# OSO-MISC-22-006_LCD_Wing.net
KiCad netlist of a schematic drawn in EAGLE
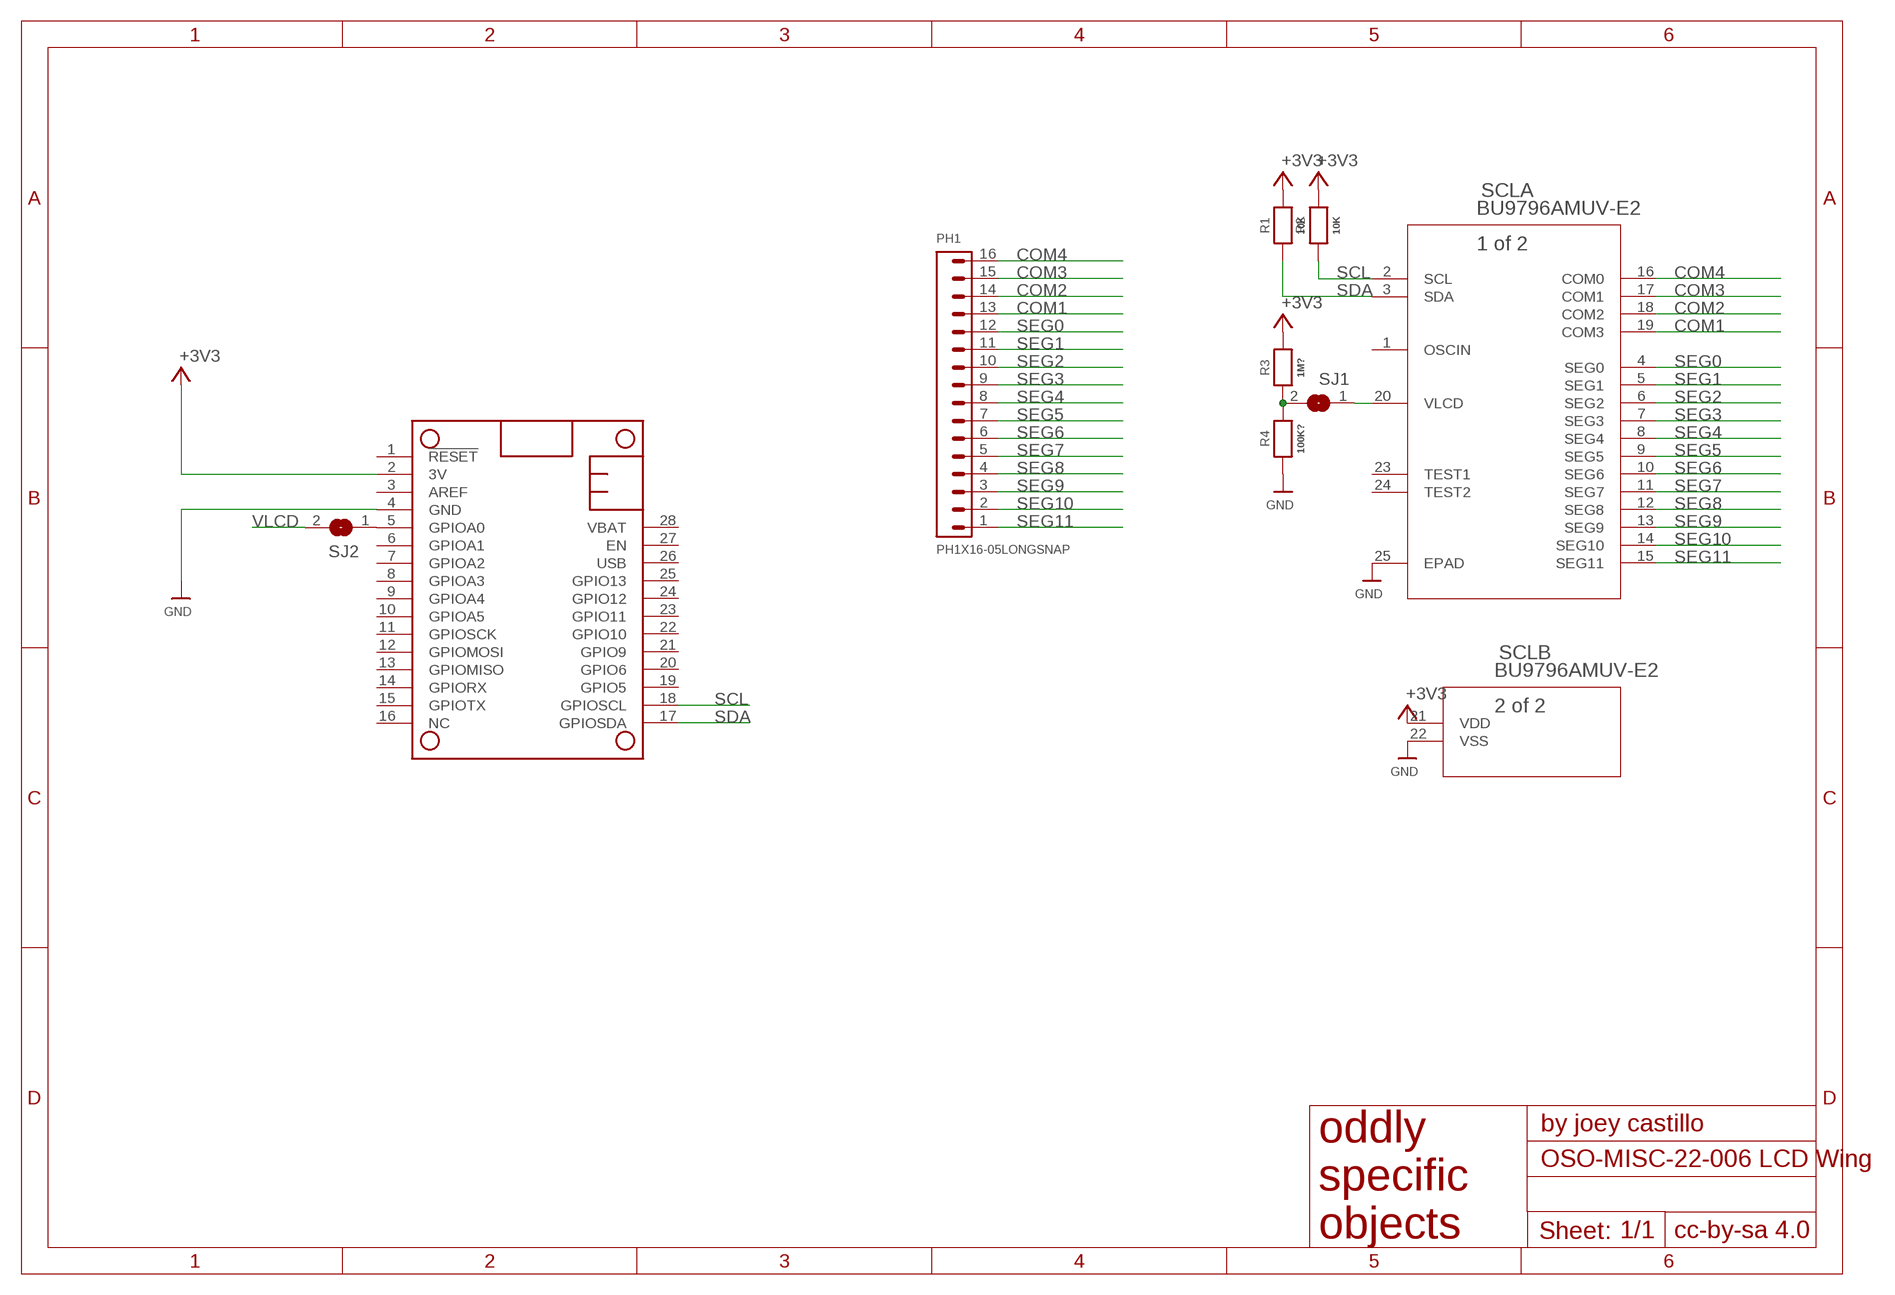
[diagram p0: schematic, sheet 1]

(export (version "E")
  (design (tool "Eeschema 10.0.6"))
  (components
    (comp (ref "MS1")
      (value "FEATHERWING")
      (footprint "eagle-import:FEATHERWING")
      (libsource (lib "eagle-import") (part "FEATHERWING"))
    )
    (comp (ref "PH1")
      (value "PH1X16-05LONGSNAP")
      (footprint "eagle-import:PHLS005-1-16")
      (libsource (lib "eagle-import") (part "PH1X16-05LONGSNAP"))
    )
    (comp (ref "R1")
      (value "10K")
      (footprint "eagle-import:_0805MP")
      (libsource (lib "eagle-import") (part "RESISTOR_0805MP"))
    )
    (comp (ref "R2")
      (value "10K")
      (footprint "eagle-import:_0805MP")
      (libsource (lib "eagle-import") (part "RESISTOR_0805MP"))
    )
    (comp (ref "R3")
      (value "1M?")
      (footprint "eagle-import:_0805MP")
      (libsource (lib "eagle-import") (part "RESISTOR_0805MP"))
    )
    (comp (ref "R4")
      (value "100K?")
      (footprint "eagle-import:_0805MP")
      (libsource (lib "eagle-import") (part "RESISTOR_0805MP"))
    )
    (comp (ref "SCL")
      (value "BU9796AMUV-E2")
      (footprint "eagle-import:VQFN024V4040_ROM")
      (fields (field (name "COPYRIGHT") "Copyright (C) 2022 Ultra Librarian. All rights reserved."))
      (libsource (lib "eagle-import") (part "BU9796AMUV-E2"))
    )
    (comp (ref "SJ1")
      (value "SOLDERJUMPERCLOSED")
      (footprint "eagle-import:SOLDERJUMPER_CLOSEDWIRE")
      (libsource (lib "eagle-import") (part "SOLDERJUMPERCLOSED"))
    )
    (comp (ref "SJ2")
      (value "SOLDERJUMPER")
      (footprint "eagle-import:SOLDERJUMPER_ARROW_NOPASTE")
      (libsource (lib "eagle-import") (part "SOLDERJUMPER"))
    )
  )
  (nets
    (net (code "1") (name "+3V3") (class "Default")
      (node (ref "MS1") (pin "2") (pinfunction "3V_2") (pintype "power_in"))
      (node (ref "R1") (pin "1") (pinfunction "1_1") (pintype "passive"))
      (node (ref "R2") (pin "1") (pinfunction "1_1") (pintype "passive"))
      (node (ref "R3") (pin "1") (pinfunction "1_1") (pintype "passive"))
      (node (ref "SCL") (pin "21") (pinfunction "VDD_21") (pintype "power_in"))
    )
    (net (code "2") (name "/COM1") (class "Default")
      (node (ref "PH1") (pin "13") (pinfunction "13_13") (pintype "bidirectional"))
      (node (ref "SCL") (pin "19") (pinfunction "COM3_19") (pintype "bidirectional"))
    )
    (net (code "3") (name "/COM2") (class "Default")
      (node (ref "PH1") (pin "14") (pinfunction "14_14") (pintype "bidirectional"))
      (node (ref "SCL") (pin "18") (pinfunction "COM2_18") (pintype "bidirectional"))
    )
    (net (code "4") (name "/COM3") (class "Default")
      (node (ref "PH1") (pin "15") (pinfunction "15_15") (pintype "bidirectional"))
      (node (ref "SCL") (pin "17") (pinfunction "COM1_17") (pintype "bidirectional"))
    )
    (net (code "5") (name "/COM4") (class "Default")
      (node (ref "PH1") (pin "16") (pinfunction "16_16") (pintype "bidirectional"))
      (node (ref "SCL") (pin "16") (pinfunction "COM0_16") (pintype "bidirectional"))
    )
    (net (code "6") (name "/SCL") (class "Default")
      (node (ref "MS1") (pin "18") (pinfunction "GPIOSCL_18") (pintype "bidirectional"))
      (node (ref "R2") (pin "2") (pinfunction "2_2") (pintype "passive"))
      (node (ref "SCL") (pin "2") (pinfunction "SCL_2") (pintype "passive"))
    )
    (net (code "7") (name "/SDA") (class "Default")
      (node (ref "MS1") (pin "17") (pinfunction "GPIOSDA_17") (pintype "bidirectional"))
      (node (ref "R1") (pin "2") (pinfunction "2_2") (pintype "passive"))
      (node (ref "SCL") (pin "3") (pinfunction "SDA_3") (pintype "passive"))
    )
    (net (code "8") (name "/SEG0") (class "Default")
      (node (ref "PH1") (pin "12") (pinfunction "12_12") (pintype "bidirectional"))
      (node (ref "SCL") (pin "4") (pinfunction "SEG0_4") (pintype "bidirectional"))
    )
    (net (code "9") (name "/SEG1") (class "Default")
      (node (ref "PH1") (pin "11") (pinfunction "11_11") (pintype "bidirectional"))
      (node (ref "SCL") (pin "5") (pinfunction "SEG1_5") (pintype "bidirectional"))
    )
    (net (code "10") (name "/SEG2") (class "Default")
      (node (ref "PH1") (pin "10") (pinfunction "10_10") (pintype "bidirectional"))
      (node (ref "SCL") (pin "6") (pinfunction "SEG2_6") (pintype "bidirectional"))
    )
    (net (code "11") (name "/SEG3") (class "Default")
      (node (ref "PH1") (pin "9") (pinfunction "9_9") (pintype "bidirectional"))
      (node (ref "SCL") (pin "7") (pinfunction "SEG3_7") (pintype "bidirectional"))
    )
    (net (code "12") (name "/SEG4") (class "Default")
      (node (ref "PH1") (pin "8") (pinfunction "8_8") (pintype "bidirectional"))
      (node (ref "SCL") (pin "8") (pinfunction "SEG4_8") (pintype "bidirectional"))
    )
    (net (code "13") (name "/SEG5") (class "Default")
      (node (ref "PH1") (pin "7") (pinfunction "7_7") (pintype "bidirectional"))
      (node (ref "SCL") (pin "9") (pinfunction "SEG5_9") (pintype "bidirectional"))
    )
    (net (code "14") (name "/SEG6") (class "Default")
      (node (ref "PH1") (pin "6") (pinfunction "6_6") (pintype "bidirectional"))
      (node (ref "SCL") (pin "10") (pinfunction "SEG6_10") (pintype "bidirectional"))
    )
    (net (code "15") (name "/SEG7") (class "Default")
      (node (ref "PH1") (pin "5") (pinfunction "5_5") (pintype "bidirectional"))
      (node (ref "SCL") (pin "11") (pinfunction "SEG7_11") (pintype "bidirectional"))
    )
    (net (code "16") (name "/SEG8") (class "Default")
      (node (ref "PH1") (pin "4") (pinfunction "4_4") (pintype "bidirectional"))
      (node (ref "SCL") (pin "12") (pinfunction "SEG8_12") (pintype "bidirectional"))
    )
    (net (code "17") (name "/SEG9") (class "Default")
      (node (ref "PH1") (pin "3") (pinfunction "3_3") (pintype "bidirectional"))
      (node (ref "SCL") (pin "13") (pinfunction "SEG9_13") (pintype "bidirectional"))
    )
    (net (code "18") (name "/SEG10") (class "Default")
      (node (ref "PH1") (pin "2") (pinfunction "2_2") (pintype "bidirectional"))
      (node (ref "SCL") (pin "14") (pinfunction "SEG10_14") (pintype "bidirectional"))
    )
    (net (code "19") (name "/SEG11") (class "Default")
      (node (ref "PH1") (pin "1") (pinfunction "1_1") (pintype "bidirectional"))
      (node (ref "SCL") (pin "15") (pinfunction "SEG11_15") (pintype "bidirectional"))
    )
    (net (code "20") (name "/USB") (class "Default")
      (node (ref "MS1") (pin "26") (pinfunction "USB_26") (pintype "power_in"))
    )
    (net (code "21") (name "/VBAT") (class "Default")
      (node (ref "MS1") (pin "28") (pinfunction "VBAT_28") (pintype "power_in"))
    )
    (net (code "22") (name "/VLCD") (class "Default")
      (node (ref "SCL") (pin "20") (pinfunction "VLCD_20") (pintype "passive"))
      (node (ref "SJ1") (pin "1") (pinfunction "1_1") (pintype "passive"))
      (node (ref "SJ2") (pin "2") (pinfunction "2_2") (pintype "passive"))
    )
    (net (code "23") (name "GND") (class "Default")
      (node (ref "MS1") (pin "4") (pinfunction "GND_4") (pintype "power_in"))
      (node (ref "R4") (pin "2") (pinfunction "2_2") (pintype "passive"))
      (node (ref "SCL") (pin "22") (pinfunction "VSS_22") (pintype "passive"))
      (node (ref "SCL") (pin "25") (pinfunction "EPAD_25") (pintype "passive"))
    )
    (net (code "24") (name "Net-(MS1-GPIOA0)") (class "Default")
      (node (ref "MS1") (pin "5") (pinfunction "GPIOA0_5") (pintype "bidirectional"))
      (node (ref "SJ2") (pin "1") (pinfunction "1_1") (pintype "passive"))
    )
    (net (code "25") (name "Net-(R3-Pad2)") (class "Default")
      (node (ref "R3") (pin "2") (pinfunction "2_2") (pintype "passive"))
      (node (ref "R4") (pin "1") (pinfunction "1_1") (pintype "passive"))
      (node (ref "SJ1") (pin "2") (pinfunction "2_2") (pintype "passive"))
    )
    (net (code "26") (name "unconnected-(MS1-AREF-Pad3)") (class "Default")
      (node (ref "MS1") (pin "3") (pinfunction "AREF_3") (pintype "passive"))
    )
    (net (code "27") (name "unconnected-(MS1-EN-Pad27)") (class "Default")
      (node (ref "MS1") (pin "27") (pinfunction "EN_27") (pintype "passive"))
    )
    (net (code "28") (name "unconnected-(MS1-GPIO5-Pad19)") (class "Default")
      (node (ref "MS1") (pin "19") (pinfunction "GPIO5_19") (pintype "bidirectional"))
    )
    (net (code "29") (name "unconnected-(MS1-GPIO6-Pad20)") (class "Default")
      (node (ref "MS1") (pin "20") (pinfunction "GPIO6_20") (pintype "bidirectional"))
    )
    (net (code "30") (name "unconnected-(MS1-GPIO9-Pad21)") (class "Default")
      (node (ref "MS1") (pin "21") (pinfunction "GPIO9_21") (pintype "bidirectional"))
    )
    (net (code "31") (name "unconnected-(MS1-GPIO10-Pad22)") (class "Default")
      (node (ref "MS1") (pin "22") (pinfunction "GPIO10_22") (pintype "bidirectional"))
    )
    (net (code "32") (name "unconnected-(MS1-GPIO11-Pad23)") (class "Default")
      (node (ref "MS1") (pin "23") (pinfunction "GPIO11_23") (pintype "bidirectional"))
    )
    (net (code "33") (name "unconnected-(MS1-GPIO12-Pad24)") (class "Default")
      (node (ref "MS1") (pin "24") (pinfunction "GPIO12_24") (pintype "bidirectional"))
    )
    (net (code "34") (name "unconnected-(MS1-GPIO13-Pad25)") (class "Default")
      (node (ref "MS1") (pin "25") (pinfunction "GPIO13_25") (pintype "bidirectional"))
    )
    (net (code "35") (name "unconnected-(MS1-GPIOA1-Pad6)") (class "Default")
      (node (ref "MS1") (pin "6") (pinfunction "GPIOA1_6") (pintype "bidirectional"))
    )
    (net (code "36") (name "unconnected-(MS1-GPIOA2-Pad7)") (class "Default")
      (node (ref "MS1") (pin "7") (pinfunction "GPIOA2_7") (pintype "bidirectional"))
    )
    (net (code "37") (name "unconnected-(MS1-GPIOA3-Pad8)") (class "Default")
      (node (ref "MS1") (pin "8") (pinfunction "GPIOA3_8") (pintype "bidirectional"))
    )
    (net (code "38") (name "unconnected-(MS1-GPIOA4-Pad9)") (class "Default")
      (node (ref "MS1") (pin "9") (pinfunction "GPIOA4_9") (pintype "bidirectional"))
    )
    (net (code "39") (name "unconnected-(MS1-GPIOA5-Pad10)") (class "Default")
      (node (ref "MS1") (pin "10") (pinfunction "GPIOA5_10") (pintype "bidirectional"))
    )
    (net (code "40") (name "unconnected-(MS1-GPIOMISO-Pad13)") (class "Default")
      (node (ref "MS1") (pin "13") (pinfunction "GPIOMISO_13") (pintype "bidirectional"))
    )
    (net (code "41") (name "unconnected-(MS1-GPIOMOSI-Pad12)") (class "Default")
      (node (ref "MS1") (pin "12") (pinfunction "GPIOMOSI_12") (pintype "bidirectional"))
    )
    (net (code "42") (name "unconnected-(MS1-GPIORX-Pad14)") (class "Default")
      (node (ref "MS1") (pin "14") (pinfunction "GPIORX_14") (pintype "bidirectional"))
    )
    (net (code "43") (name "unconnected-(MS1-GPIOSCK-Pad11)") (class "Default")
      (node (ref "MS1") (pin "11") (pinfunction "GPIOSCK_11") (pintype "bidirectional"))
    )
    (net (code "44") (name "unconnected-(MS1-GPIOTX-Pad15)") (class "Default")
      (node (ref "MS1") (pin "15") (pinfunction "GPIOTX_15") (pintype "bidirectional"))
    )
    (net (code "45") (name "unconnected-(MS1-NC-Pad16)") (class "Default")
      (node (ref "MS1") (pin "16") (pinfunction "NC_16") (pintype "passive"))
    )
    (net (code "46") (name "unconnected-(MS1-~{RESET}-Pad1)") (class "Default")
      (node (ref "MS1") (pin "1") (pinfunction "~{RESET}_1") (pintype "input"))
    )
    (net (code "47") (name "unconnected-(SCLA-OSCIN-Pad1)") (class "Default")
      (node (ref "SCL") (pin "1") (pinfunction "OSCIN_1") (pintype "passive"))
    )
    (net (code "48") (name "unconnected-(SCLA-TEST1-Pad23)") (class "Default")
      (node (ref "SCL") (pin "23") (pinfunction "TEST1_23") (pintype "bidirectional"))
    )
    (net (code "49") (name "unconnected-(SCLA-TEST2-Pad24)") (class "Default")
      (node (ref "SCL") (pin "24") (pinfunction "TEST2_24") (pintype "bidirectional"))
    )
  )
)
